# SCH1.net
KiCad netlist of a schematic drawn in EAGLE
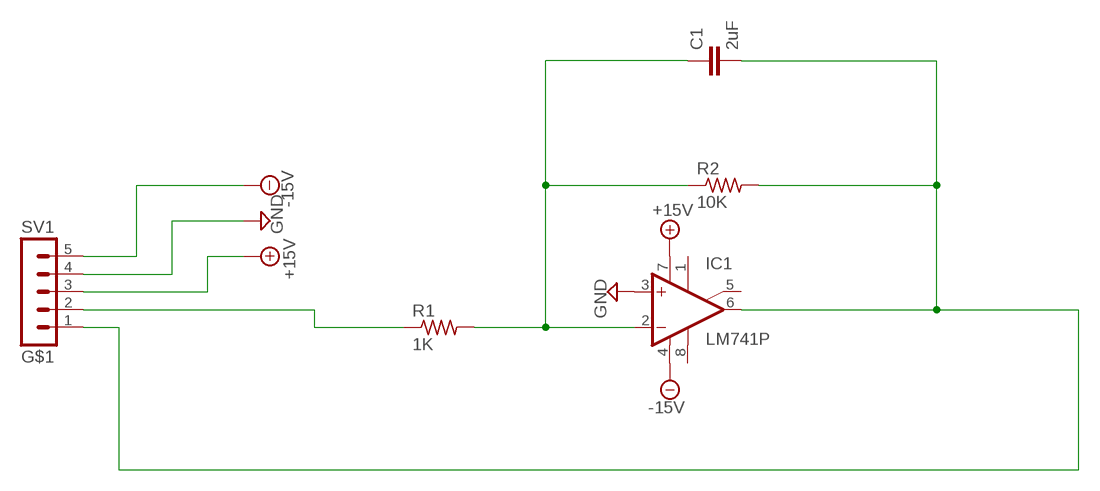
[diagram p0: schematic, sheet 1]

(export (version "E")
  (design (tool "Eeschema 10.0.6"))
  (components
    (comp (ref "C1")
      (value "2uF")
      (footprint "eagle-import:C0603")
      (libsource (lib "eagle-import") (part "C-EUC0603"))
    )
    (comp (ref "IC1")
      (value "LM741P")
      (footprint "eagle-import:DIL08")
      (libsource (lib "eagle-import") (part "741PLM"))
    )
    (comp (ref "R1")
      (value "1K")
      (footprint "eagle-import:0204_5")
      (libsource (lib "eagle-import") (part "R-US_0204/5"))
    )
    (comp (ref "R2")
      (value "10K")
      (footprint "eagle-import:0204V")
      (libsource (lib "eagle-import") (part "R-US_0204/2V"))
    )
    (comp (ref "SV1")
      (value "G$1")
      (footprint "eagle-import:MA05-1")
      (libsource (lib "eagle-import") (part "MA05-1"))
    )
  )
  (nets
    (net (code "1") (name "+15V") (class "Default")
      (node (ref "IC1") (pin "7") (pinfunction "V+_7") (pintype "power_in"))
      (node (ref "SV1") (pin "3") (pinfunction "3_3") (pintype "passive"))
    )
    (net (code "2") (name "-15V") (class "Default")
      (node (ref "IC1") (pin "4") (pinfunction "V-_4") (pintype "power_in"))
      (node (ref "SV1") (pin "5") (pinfunction "5_5") (pintype "passive"))
    )
    (net (code "3") (name "GND") (class "Default")
      (node (ref "IC1") (pin "3") (pinfunction "+IN_3") (pintype "input"))
      (node (ref "SV1") (pin "4") (pinfunction "4_4") (pintype "passive"))
    )
    (net (code "4") (name "Net-(IC1--IN)") (class "Default")
      (node (ref "C1") (pin "1") (pinfunction "1_1") (pintype "passive"))
      (node (ref "IC1") (pin "2") (pinfunction "-IN_2") (pintype "input"))
      (node (ref "R1") (pin "2") (pinfunction "2_2") (pintype "passive"))
      (node (ref "R2") (pin "1") (pinfunction "1_1") (pintype "passive"))
    )
    (net (code "5") (name "Net-(IC1-OUT)") (class "Default")
      (node (ref "C1") (pin "2") (pinfunction "2_2") (pintype "passive"))
      (node (ref "IC1") (pin "6") (pinfunction "OUT_6") (pintype "output"))
      (node (ref "R2") (pin "2") (pinfunction "2_2") (pintype "passive"))
      (node (ref "SV1") (pin "1") (pinfunction "1_1") (pintype "passive"))
    )
    (net (code "6") (name "Net-(R1-Pad1)") (class "Default")
      (node (ref "R1") (pin "1") (pinfunction "1_1") (pintype "passive"))
      (node (ref "SV1") (pin "2") (pinfunction "2_2") (pintype "passive"))
    )
    (net (code "7") (name "unconnected-(IC1-ON1-Pad1)") (class "Default")
      (node (ref "IC1") (pin "1") (pinfunction "ON1_1") (pintype "passive"))
    )
    (net (code "8") (name "unconnected-(IC1-ON2-Pad5)") (class "Default")
      (node (ref "IC1") (pin "5") (pinfunction "ON2_5") (pintype "passive"))
    )
    (net (code "9") (name "unconnected-(IC1-OPT-Pad8)") (class "Default")
      (node (ref "IC1") (pin "8") (pinfunction "OPT_8") (pintype "passive"))
    )
  )
)
